# SP.net
KiCad netlist of a schematic drawn in EAGLE
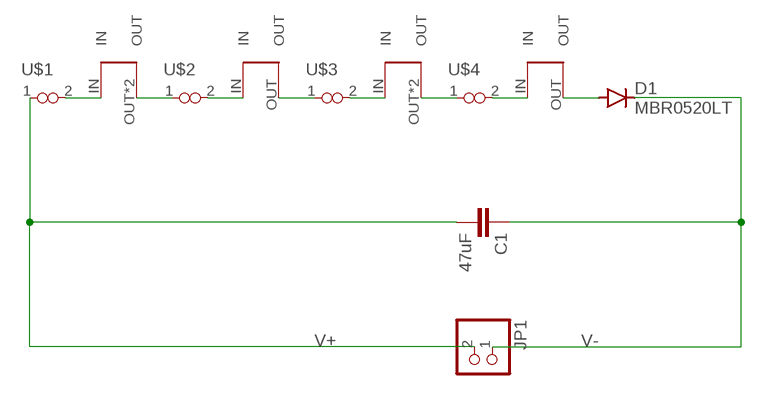
[diagram p0: schematic, sheet 1]

(export (version "E")
  (design (tool "Eeschema 10.0.6"))
  (components
    (comp (ref "C1")
      (value "47uF")
      (footprint "eagle-import:C1210")
      (libsource (lib "eagle-import") (part "C-EUC1210"))
    )
    (comp (ref "D1")
      (value "MBR0520LT")
      (footprint "eagle-import:SOD123")
      (libsource (lib "eagle-import") (part "MBR0520LT"))
    )
    (comp (ref "JP1")
      (value "PINHD-1X2")
      (footprint "eagle-import:1X02")
      (libsource (lib "eagle-import") (part "PINHD-1X2"))
    )
    (comp (ref "U$1")
      (value "VIAS-CONNECT")
      (footprint "eagle-import:VIAS-CONNECT")
      (libsource (lib "eagle-import") (part "VIAS-CONNECT"))
    )
    (comp (ref "U$2")
      (value "VIAS-CONNECT")
      (footprint "eagle-import:VIAS-CONNECT")
      (libsource (lib "eagle-import") (part "VIAS-CONNECT"))
    )
    (comp (ref "U$3")
      (value "VIAS-CONNECT")
      (footprint "eagle-import:VIAS-CONNECT")
      (libsource (lib "eagle-import") (part "VIAS-CONNECT"))
    )
    (comp (ref "U$4")
      (value "VIAS-CONNECT")
      (footprint "eagle-import:VIAS-CONNECT")
      (libsource (lib "eagle-import") (part "VIAS-CONNECT"))
    )
    (comp (ref "U$5")
      (value "SOLAR_1")
      (footprint "eagle-import:SOLAR_1")
      (libsource (lib "eagle-import") (part "SOLAR_1"))
    )
    (comp (ref "U$6")
      (value "SOLAR_0")
      (footprint "eagle-import:SOLAR_0")
      (libsource (lib "eagle-import") (part "SOLAR_0"))
    )
    (comp (ref "U$7")
      (value "SOLAR_0")
      (footprint "eagle-import:SOLAR_0")
      (libsource (lib "eagle-import") (part "SOLAR_0"))
    )
    (comp (ref "U$8")
      (value "SOLAR_1")
      (footprint "eagle-import:SOLAR_1")
      (libsource (lib "eagle-import") (part "SOLAR_1"))
    )
  )
  (nets
    (net (code "1") (name "/V+") (class "Default")
      (node (ref "C1") (pin "2") (pinfunction "2_2") (pintype "passive"))
      (node (ref "JP1") (pin "2") (pinfunction "2_2") (pintype "passive"))
      (node (ref "U$1") (pin "1") (pinfunction "1_1") (pintype "passive"))
    )
    (net (code "2") (name "/V-") (class "Default")
      (node (ref "C1") (pin "1") (pinfunction "1_1") (pintype "passive"))
      (node (ref "D1") (pin "C") (pinfunction "C_C") (pintype "passive"))
      (node (ref "JP1") (pin "1") (pinfunction "1_1") (pintype "passive"))
    )
    (net (code "3") (name "Net-(D1-PadA)") (class "Default")
      (node (ref "D1") (pin "A") (pinfunction "A_A") (pintype "passive"))
      (node (ref "U$8") (pin "OUT") (pinfunction "OUT_OUT") (pintype "bidirectional"))
    )
    (net (code "4") (name "Net-(U$1-Pad2)") (class "Default")
      (node (ref "U$1") (pin "2") (pinfunction "2_2") (pintype "passive"))
      (node (ref "U$7") (pin "IN") (pinfunction "IN_IN") (pintype "bidirectional"))
    )
    (net (code "5") (name "Net-(U$2-Pad1)") (class "Default")
      (node (ref "U$2") (pin "1") (pinfunction "1_1") (pintype "passive"))
      (node (ref "U$7") (pin "OUT") (pinfunction "OUT_OUT") (pintype "bidirectional"))
      (node (ref "U$7") (pin "OUT-21") (pinfunction "OUT_OUT-21") (pintype "bidirectional"))
    )
    (net (code "6") (name "Net-(U$2-Pad2)") (class "Default")
      (node (ref "U$2") (pin "2") (pinfunction "2_2") (pintype "passive"))
      (node (ref "U$5") (pin "IN") (pinfunction "IN_IN") (pintype "bidirectional"))
    )
    (net (code "7") (name "Net-(U$3-Pad1)") (class "Default")
      (node (ref "U$3") (pin "1") (pinfunction "1_1") (pintype "passive"))
      (node (ref "U$5") (pin "OUT") (pinfunction "OUT_OUT") (pintype "bidirectional"))
    )
    (net (code "8") (name "Net-(U$3-Pad2)") (class "Default")
      (node (ref "U$3") (pin "2") (pinfunction "2_2") (pintype "passive"))
      (node (ref "U$6") (pin "IN") (pinfunction "IN_IN") (pintype "bidirectional"))
    )
    (net (code "9") (name "Net-(U$4-Pad1)") (class "Default")
      (node (ref "U$4") (pin "1") (pinfunction "1_1") (pintype "passive"))
      (node (ref "U$6") (pin "OUT") (pinfunction "OUT_OUT") (pintype "bidirectional"))
      (node (ref "U$6") (pin "OUT-21") (pinfunction "OUT_OUT-21") (pintype "bidirectional"))
    )
    (net (code "10") (name "Net-(U$4-Pad2)") (class "Default")
      (node (ref "U$4") (pin "2") (pinfunction "2_2") (pintype "passive"))
      (node (ref "U$8") (pin "IN") (pinfunction "IN_IN") (pintype "bidirectional"))
    )
  )
)
